# DRV2605.net
KiCad netlist of a schematic drawn in EAGLE
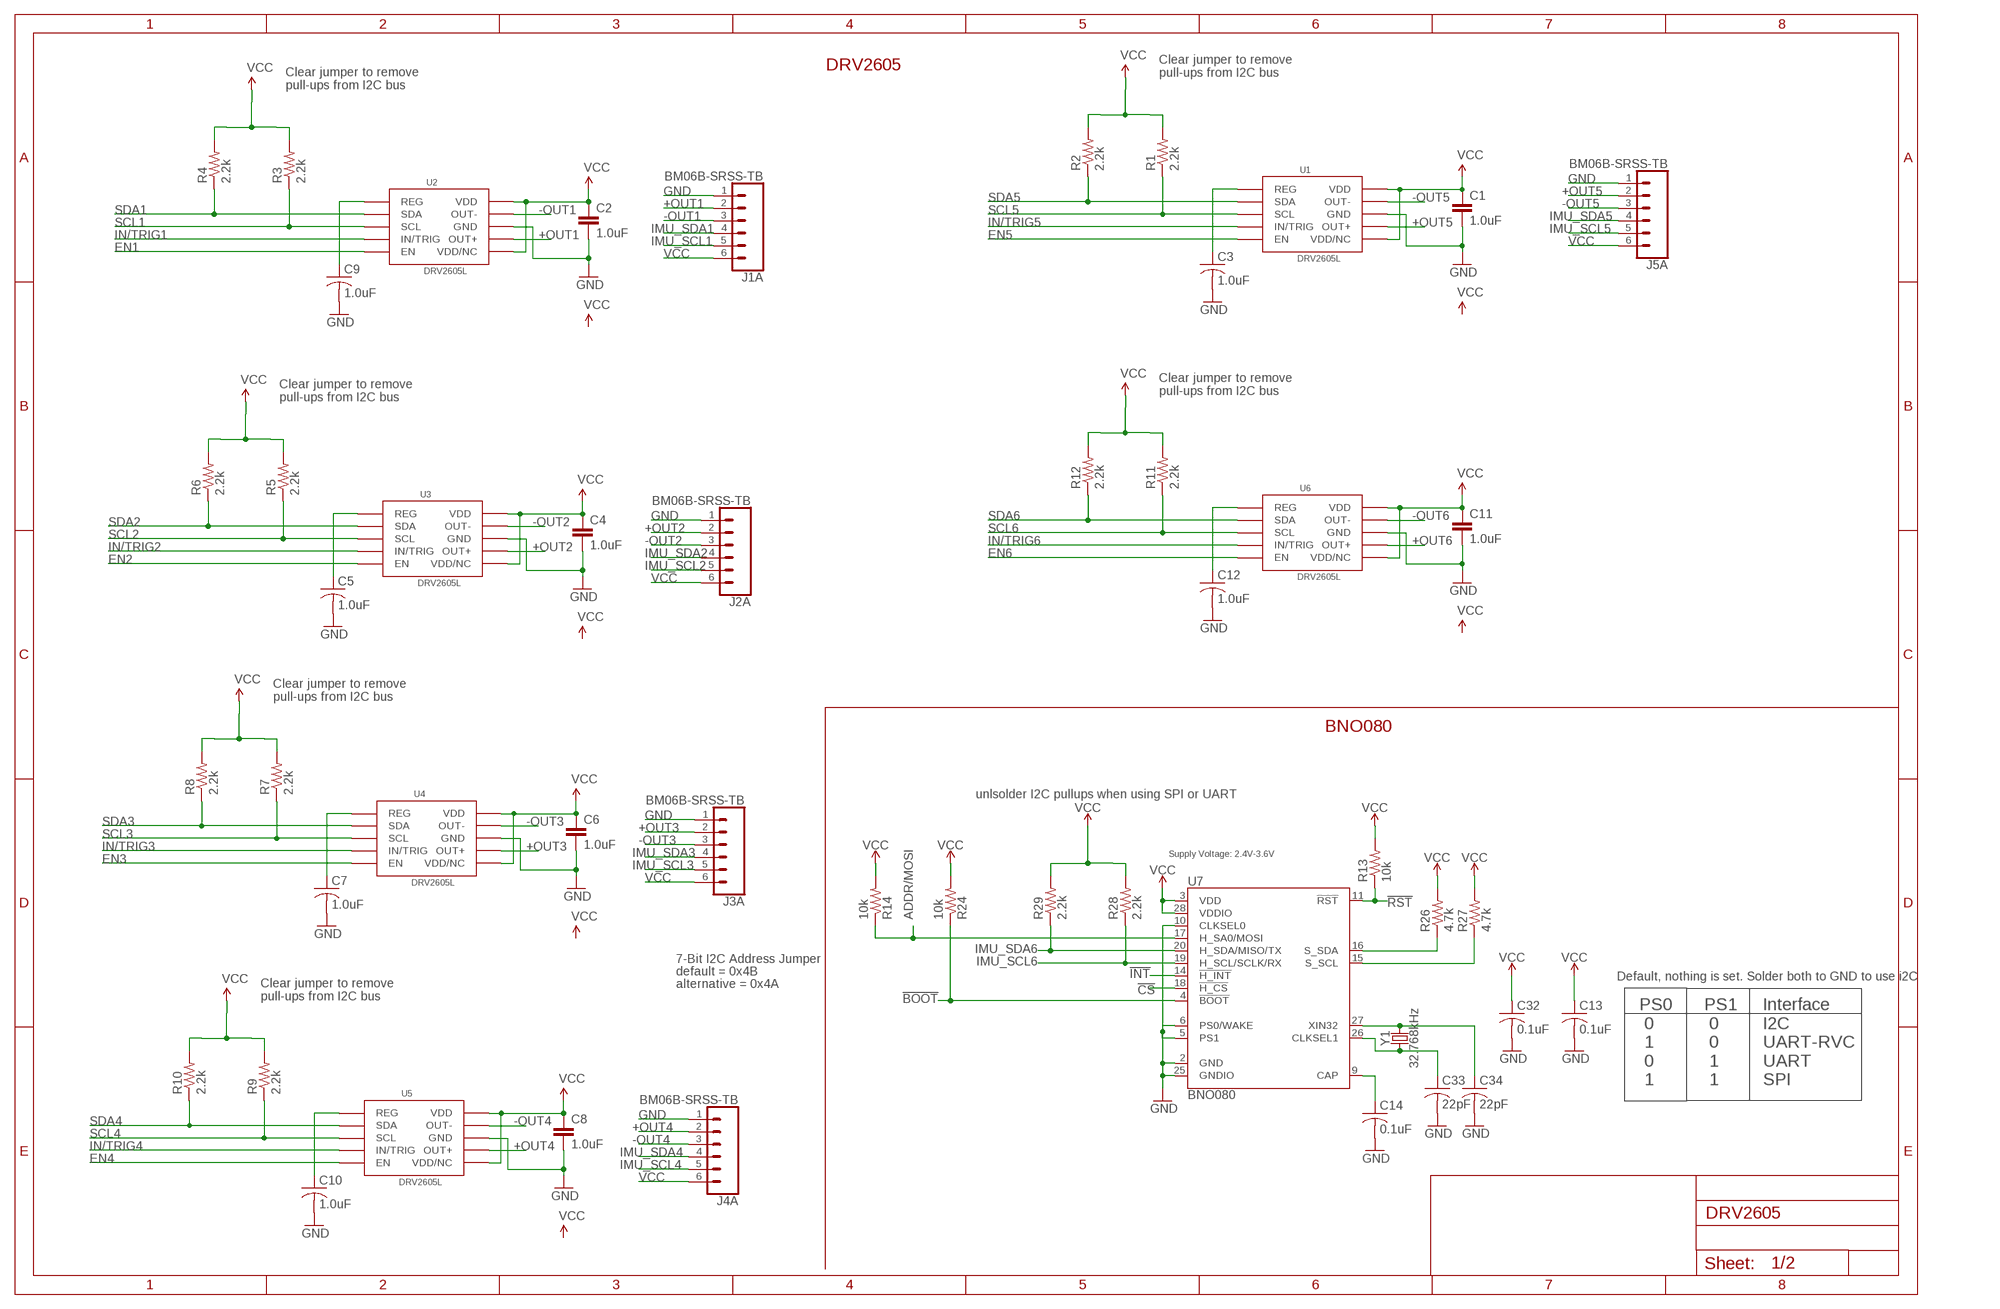
[diagram p0: schematic, sheet 1]
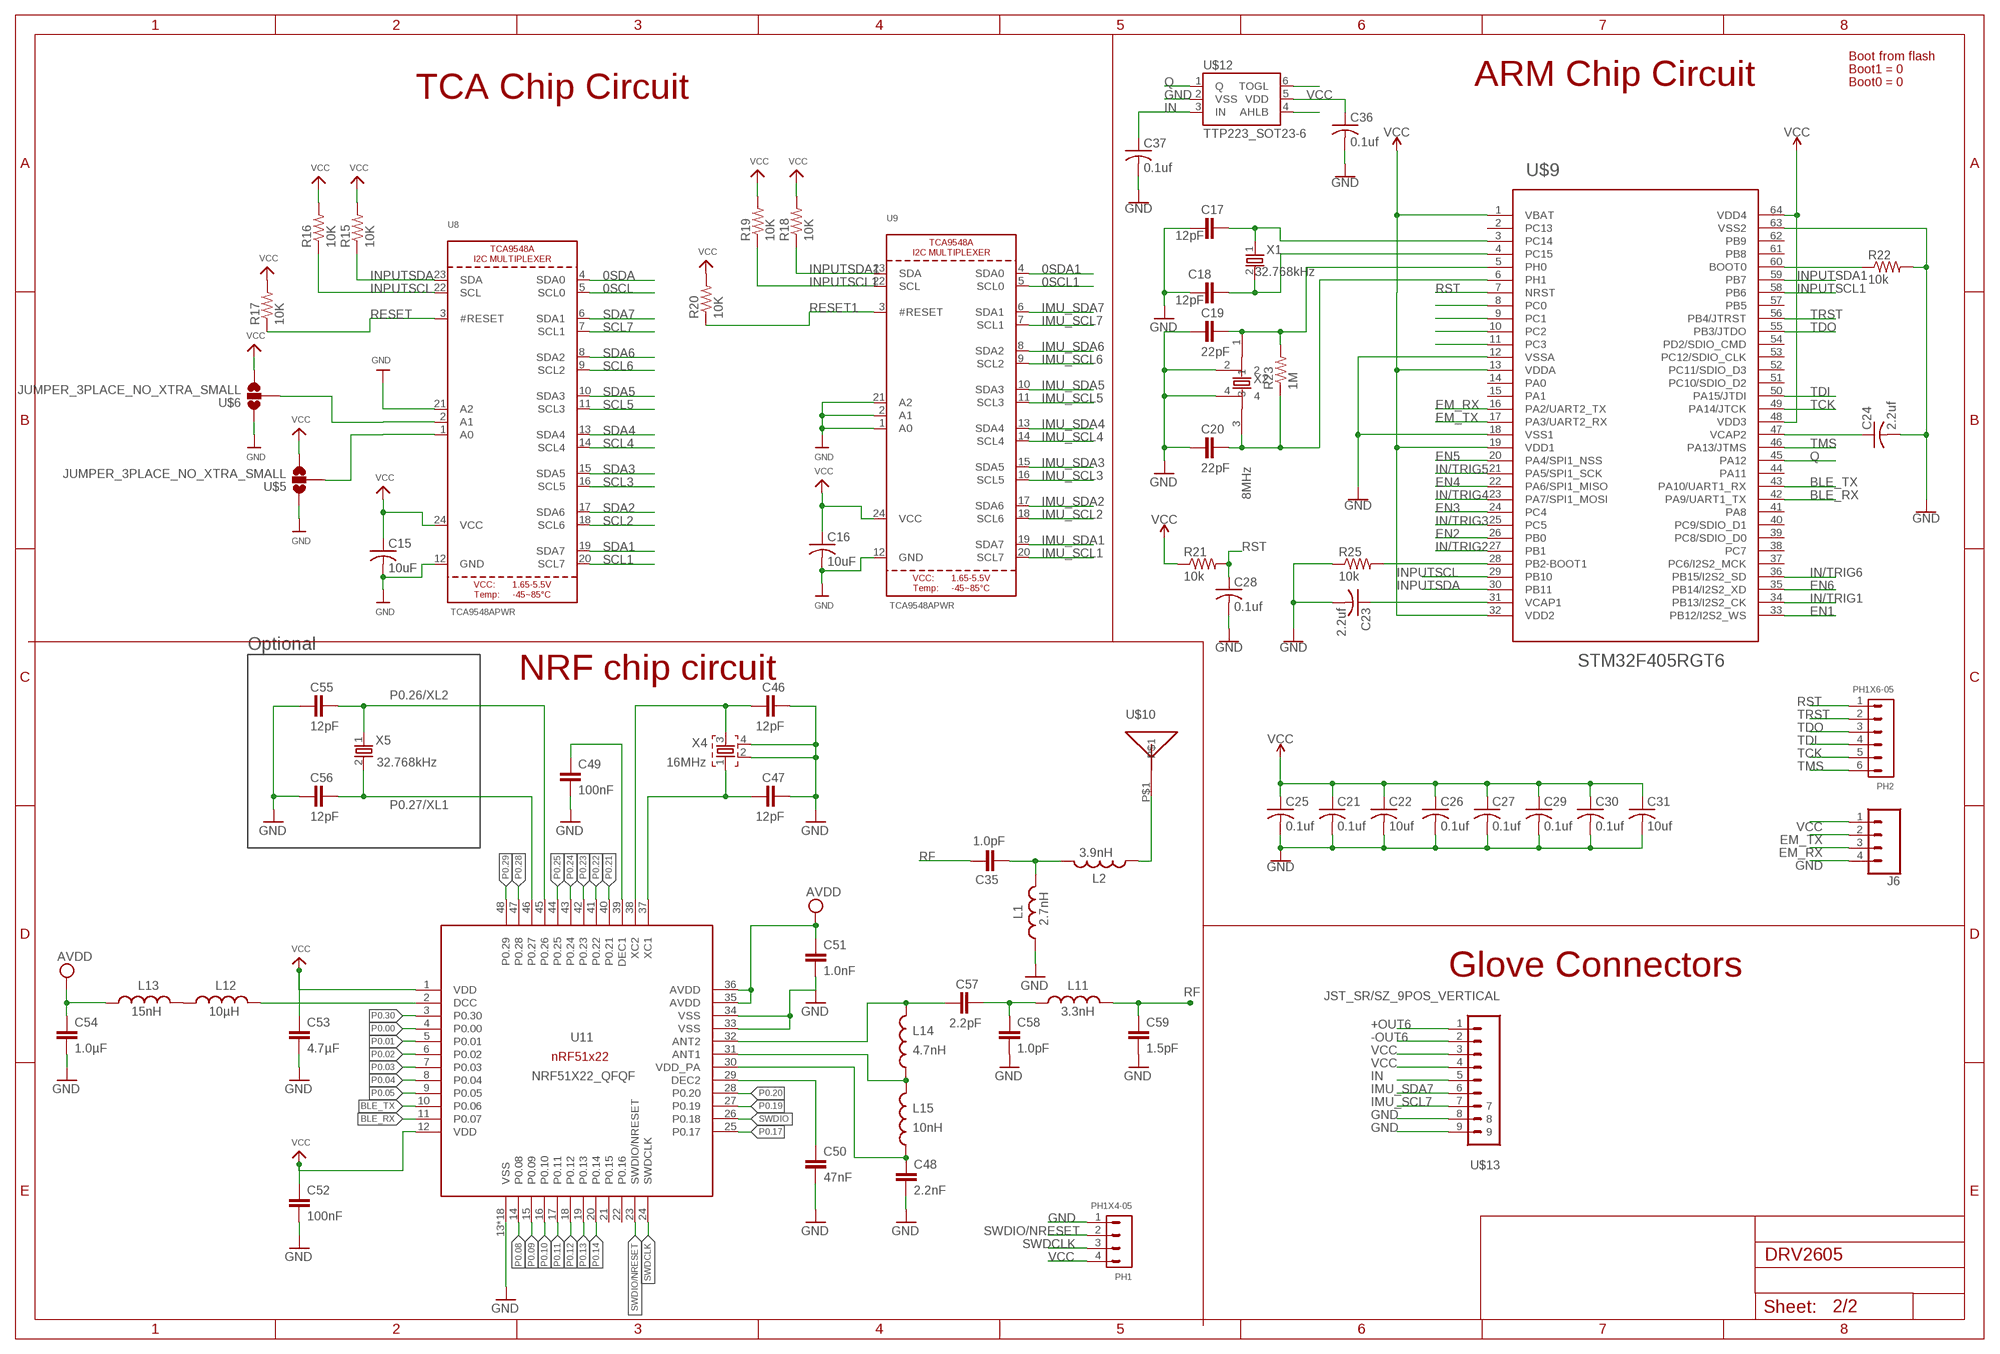
[diagram p1: schematic, sheet 2]

(export (version "E")
  (design (tool "Eeschema 10.0.6"))
  (components
    (comp (ref "C15")
      (value "10uF")
      (footprint "eagle-import:C0402")
      (libsource (lib "eagle-import") (part "resistor_348_C-USC0402"))
    )
    (comp (ref "C16")
      (value "10uF")
      (footprint "eagle-import:C0402")
      (libsource (lib "eagle-import") (part "resistor_348_C-USC0402"))
    )
    (comp (ref "C17")
      (value "12pF")
      (footprint "eagle-import:RESC0402_N")
      (libsource (lib "eagle-import") (part "CAPACITOR_0402_N"))
    )
    (comp (ref "C18")
      (value "12pF")
      (footprint "eagle-import:RESC0402_N")
      (libsource (lib "eagle-import") (part "CAPACITOR_0402_N"))
    )
    (comp (ref "C19")
      (value "22pF")
      (footprint "eagle-import:RESC0402_N")
      (libsource (lib "eagle-import") (part "CAPACITOR_0402_N"))
    )
    (comp (ref "C20")
      (value "22pF")
      (footprint "eagle-import:RESC0402_N")
      (libsource (lib "eagle-import") (part "CAPACITOR_0402_N"))
    )
    (comp (ref "C21")
      (value "0.1uf")
      (footprint "eagle-import:C0402")
      (libsource (lib "eagle-import") (part "C-USC0402"))
    )
    (comp (ref "C22")
      (value "10uf")
      (footprint "eagle-import:C0402")
      (libsource (lib "eagle-import") (part "C-USC0402"))
    )
    (comp (ref "C23")
      (value "2.2uf")
      (footprint "eagle-import:C0402")
      (libsource (lib "eagle-import") (part "C-USC0402"))
    )
    (comp (ref "C24")
      (value "2.2uf")
      (footprint "eagle-import:C0402")
      (libsource (lib "eagle-import") (part "C-USC0402"))
    )
    (comp (ref "C25")
      (value "0.1uf")
      (footprint "eagle-import:C0402")
      (libsource (lib "eagle-import") (part "C-USC0402"))
    )
    (comp (ref "C26")
      (value "0.1uf")
      (footprint "eagle-import:C0402")
      (libsource (lib "eagle-import") (part "C-USC0402"))
    )
    (comp (ref "C27")
      (value "0.1uf")
      (footprint "eagle-import:C0402")
      (libsource (lib "eagle-import") (part "C-USC0402"))
    )
    (comp (ref "C28")
      (value "0.1uf")
      (footprint "eagle-import:C0402")
      (libsource (lib "eagle-import") (part "C-USC0402"))
    )
    (comp (ref "C29")
      (value "0.1uf")
      (footprint "eagle-import:C0402")
      (libsource (lib "eagle-import") (part "C-USC0402"))
    )
    (comp (ref "C30")
      (value "0.1uf")
      (footprint "eagle-import:C0402")
      (libsource (lib "eagle-import") (part "C-USC0402"))
    )
    (comp (ref "C31")
      (value "10uf")
      (footprint "eagle-import:C0402")
      (libsource (lib "eagle-import") (part "C-USC0402"))
    )
    (comp (ref "C35")
      (value "1.0pF")
      (footprint "eagle-import:RESC0402_N")
      (libsource (lib "eagle-import") (part "CAPACITOR_0402_N"))
    )
    (comp (ref "C36")
      (value "0.1uf")
      (footprint "eagle-import:C0402")
      (libsource (lib "eagle-import") (part "C-USC0402"))
    )
    (comp (ref "C37")
      (value "0.1uf")
      (footprint "eagle-import:C0402")
      (libsource (lib "eagle-import") (part "C-USC0402"))
    )
    (comp (ref "C46")
      (value "12pF")
      (footprint "eagle-import:RESC0402_N")
      (libsource (lib "eagle-import") (part "CAPACITOR_0402_N"))
    )
    (comp (ref "C47")
      (value "12pF")
      (footprint "eagle-import:RESC0402_N")
      (libsource (lib "eagle-import") (part "CAPACITOR_0402_N"))
    )
    (comp (ref "C48")
      (value "2.2nF")
      (footprint "eagle-import:RESC0402_N")
      (libsource (lib "eagle-import") (part "CAPACITOR_0402_N"))
    )
    (comp (ref "C49")
      (value "100nF")
      (footprint "eagle-import:RESC0402_N")
      (libsource (lib "eagle-import") (part "CAPACITOR_0402_N"))
    )
    (comp (ref "C50")
      (value "47nF")
      (footprint "eagle-import:RESC0402_N")
      (libsource (lib "eagle-import") (part "CAPACITOR_0402_N"))
    )
    (comp (ref "C51")
      (value "1.0nF")
      (footprint "eagle-import:RESC0402_N")
      (libsource (lib "eagle-import") (part "CAPACITOR_0402_N"))
    )
    (comp (ref "C52")
      (value "100nF")
      (footprint "eagle-import:RESC0402_N")
      (libsource (lib "eagle-import") (part "CAPACITOR_0402_N"))
    )
    (comp (ref "C53")
      (value "4.7µF")
      (footprint "eagle-import:RESC0603_N")
      (libsource (lib "eagle-import") (part "CAPACITOR_0603_N"))
    )
    (comp (ref "C54")
      (value "1.0µF")
      (footprint "eagle-import:RESC0603_N")
      (libsource (lib "eagle-import") (part "CAPACITOR_0603_N"))
    )
    (comp (ref "C55")
      (value "12pF")
      (footprint "eagle-import:RESC0402_N")
      (libsource (lib "eagle-import") (part "CAPACITOR_0402_N"))
    )
    (comp (ref "C56")
      (value "12pF")
      (footprint "eagle-import:RESC0402_N")
      (libsource (lib "eagle-import") (part "CAPACITOR_0402_N"))
    )
    (comp (ref "C57")
      (value "2.2pF")
      (footprint "eagle-import:RESC0402_N")
      (libsource (lib "eagle-import") (part "CAPACITOR_0402_N"))
    )
    (comp (ref "C58")
      (value "1.0pF")
      (footprint "eagle-import:RESC0402_N")
      (libsource (lib "eagle-import") (part "CAPACITOR_0402_N"))
    )
    (comp (ref "C59")
      (value "1.5pF")
      (footprint "eagle-import:RESC0402_N")
      (libsource (lib "eagle-import") (part "CAPACITOR_0402_N"))
    )
    (comp (ref "J6")
      (value "CONN_04")
      (footprint "eagle-import:1X04")
      (libsource (lib "eagle-import") (part "CONN_04"))
    )
    (comp (ref "L1")
      (value "2.7nH")
      (footprint "eagle-import:RESC0402_N")
      (libsource (lib "eagle-import") (part "INDUCTOR_0402_N"))
    )
    (comp (ref "L2")
      (value "3.9nH")
      (footprint "eagle-import:RESC0402_N")
      (libsource (lib "eagle-import") (part "INDUCTOR_0402_N"))
    )
    (comp (ref "L11")
      (value "3.3nH")
      (footprint "eagle-import:RESC0402_N")
      (libsource (lib "eagle-import") (part "INDUCTOR_0402_N"))
    )
    (comp (ref "L12")
      (value "10µH")
      (footprint "eagle-import:RESC0603_N")
      (libsource (lib "eagle-import") (part "INDUCTOR_0603_N"))
    )
    (comp (ref "L13")
      (value "15nH")
      (footprint "eagle-import:RESC0402_N")
      (libsource (lib "eagle-import") (part "INDUCTOR_0402_N"))
    )
    (comp (ref "L14")
      (value "4.7nH")
      (footprint "eagle-import:RESC0402_N")
      (libsource (lib "eagle-import") (part "INDUCTOR_0402_N"))
    )
    (comp (ref "L15")
      (value "10nH")
      (footprint "eagle-import:RESC0402_N")
      (libsource (lib "eagle-import") (part "INDUCTOR_0402_N"))
    )
    (comp (ref "PH1")
      (value "PH1X4-05")
      (footprint "eagle-import:PH005-1-4")
      (libsource (lib "eagle-import") (part "PH1X4-05"))
    )
    (comp (ref "PH2")
      (value "PH1X6-05")
      (footprint "eagle-import:PH005-1-6")
      (libsource (lib "eagle-import") (part "PH1X6-05"))
    )
    (comp (ref "R15")
      (value "10K")
      (footprint "eagle-import:R0402")
      (libsource (lib "eagle-import") (part "R-US_R0402"))
    )
    (comp (ref "R16")
      (value "10K")
      (footprint "eagle-import:R0402")
      (libsource (lib "eagle-import") (part "R-US_R0402"))
    )
    (comp (ref "R17")
      (value "10K")
      (footprint "eagle-import:R0402")
      (libsource (lib "eagle-import") (part "R-US_R0402"))
    )
    (comp (ref "R18")
      (value "10K")
      (footprint "eagle-import:R0402")
      (libsource (lib "eagle-import") (part "R-US_R0402"))
    )
    (comp (ref "R19")
      (value "10K")
      (footprint "eagle-import:R0402")
      (libsource (lib "eagle-import") (part "R-US_R0402"))
    )
    (comp (ref "R20")
      (value "10K")
      (footprint "eagle-import:R0402")
      (libsource (lib "eagle-import") (part "R-US_R0402"))
    )
    (comp (ref "R21")
      (value "10k")
      (footprint "eagle-import:R0402")
      (libsource (lib "eagle-import") (part "resistor_348_R-US_R0402"))
    )
    (comp (ref "R22")
      (value "10k")
      (footprint "eagle-import:R0402")
      (libsource (lib "eagle-import") (part "resistor_348_R-US_R0402"))
    )
    (comp (ref "R23")
      (value "1M")
      (footprint "eagle-import:R0402")
      (libsource (lib "eagle-import") (part "resistor_348_R-US_R0402"))
    )
    (comp (ref "R25")
      (value "10k")
      (footprint "eagle-import:R0402")
      (libsource (lib "eagle-import") (part "resistor_348_R-US_R0402"))
    )
    (comp (ref "U$5")
      (value "JUMPER_3PLACE_NO_XTRA_SMALL")
      (footprint "eagle-import:XTRA_SMALL_JUMPER_3_NO")
      (libsource (lib "eagle-import") (part "JUMPER_3PLACE_NO_XTRA_SMALL"))
    )
    (comp (ref "U$6")
      (value "JUMPER_3PLACE_NO_XTRA_SMALL")
      (footprint "eagle-import:XTRA_SMALL_JUMPER_3_NO")
      (libsource (lib "eagle-import") (part "JUMPER_3PLACE_NO_XTRA_SMALL"))
    )
    (comp (ref "U$9")
      (value "STM32F405RGT6")
      (footprint "eagle-import:TQFP64")
      (libsource (lib "eagle-import") (part "STM32F405RG"))
    )
    (comp (ref "U$10")
      (value "ANT_2450AT18B100E")
      (footprint "eagle-import:2450AT18B100E")
      (libsource (lib "eagle-import") (part "ANT_2450AT18B100E"))
    )
    (comp (ref "U$12")
      (value "TTP223_SOT23-6")
      (footprint "eagle-import:SOT23-6")
      (libsource (lib "eagle-import") (part "TTP223_SOT23-6"))
    )
    (comp (ref "U$13")
      (value "JST_SR/SZ_9POS_VERTICAL")
      (footprint "eagle-import:JST_SR_SZ_VERTICA_9POS")
      (libsource (lib "eagle-import") (part "JST_SR/SZ_9POS_VERTICAL"))
    )
    (comp (ref "U8")
      (value "TCA9548APWR")
      (footprint "eagle-import:TSSOP24")
      (libsource (lib "eagle-import") (part "TCA9548A"))
    )
    (comp (ref "U9")
      (value "TCA9548APWR")
      (footprint "eagle-import:TSSOP24")
      (libsource (lib "eagle-import") (part "TCA9548A"))
    )
    (comp (ref "U11")
      (value "NRF51X22_QFQF")
      (footprint "eagle-import:QFN40P600X600X90-48_N")
      (libsource (lib "eagle-import") (part "NRF51X22_QFQF"))
    )
    (comp (ref "X1")
      (value "32.768kHz")
      (footprint "eagle-import:XTAL_3215_N")
      (libsource (lib "eagle-import") (part "XTAL_32KHZ"))
    )
    (comp (ref "X2")
      (value "8MHz")
      (footprint "eagle-import:CRYSTAL-SMD-5X3.2-4PAD")
      (libsource (lib "eagle-import") (part "CRYSTAL_5X3.2MM_4PAD"))
    )
    (comp (ref "X4")
      (value "16MHz")
      (footprint "eagle-import:BT-XTAL_2016_N")
      (libsource (lib "eagle-import") (part "XTAL_32MHZ"))
    )
    (comp (ref "X5")
      (value "32.768kHz")
      (footprint "eagle-import:XTAL_3215_N")
      (libsource (lib "eagle-import") (part "XTAL_32KHZ"))
    )
    (comp (ref "C1")
      (value "1.0uF")
      (footprint "eagle-import:0402-CAP")
      (libsource (lib "eagle-import") (part "1.0UF-16V-10%(0402)"))
    )
    (comp (ref "C2")
      (value "1.0uF")
      (footprint "eagle-import:0402-CAP")
      (libsource (lib "eagle-import") (part "1.0UF-16V-10%(0402)"))
    )
    (comp (ref "C3")
      (value "1.0uF")
      (footprint "eagle-import:C0402")
      (libsource (lib "eagle-import") (part "C-USC0402"))
    )
    (comp (ref "C4")
      (value "1.0uF")
      (footprint "eagle-import:0402-CAP")
      (libsource (lib "eagle-import") (part "1.0UF-16V-10%(0402)"))
    )
    (comp (ref "C5")
      (value "1.0uF")
      (footprint "eagle-import:C0402")
      (libsource (lib "eagle-import") (part "C-USC0402"))
    )
    (comp (ref "C6")
      (value "1.0uF")
      (footprint "eagle-import:0402-CAP")
      (libsource (lib "eagle-import") (part "1.0UF-16V-10%(0402)"))
    )
    (comp (ref "C7")
      (value "1.0uF")
      (footprint "eagle-import:C0402")
      (libsource (lib "eagle-import") (part "C-USC0402"))
    )
    (comp (ref "C8")
      (value "1.0uF")
      (footprint "eagle-import:0402-CAP")
      (libsource (lib "eagle-import") (part "1.0UF-16V-10%(0402)"))
    )
    (comp (ref "C9")
      (value "1.0uF")
      (footprint "eagle-import:C0402")
      (libsource (lib "eagle-import") (part "C-USC0402"))
    )
    (comp (ref "C10")
      (value "1.0uF")
      (footprint "eagle-import:C0402")
      (libsource (lib "eagle-import") (part "C-USC0402"))
    )
    (comp (ref "C11")
      (value "1.0uF")
      (footprint "eagle-import:0402-CAP")
      (libsource (lib "eagle-import") (part "1.0UF-16V-10%(0402)"))
    )
    (comp (ref "C12")
      (value "1.0uF")
      (footprint "eagle-import:C0402")
      (libsource (lib "eagle-import") (part "C-USC0402"))
    )
    (comp (ref "C13")
      (value "0.1uF")
      (footprint "eagle-import:C0402")
      (libsource (lib "eagle-import") (part "C-USC0402"))
    )
    (comp (ref "C14")
      (value "0.1uF")
      (footprint "eagle-import:C0402")
      (libsource (lib "eagle-import") (part "C-USC0402"))
    )
    (comp (ref "C32")
      (value "0.1uF")
      (footprint "eagle-import:C0402")
      (libsource (lib "eagle-import") (part "C-USC0402"))
    )
    (comp (ref "C33")
      (value "22pF")
      (footprint "eagle-import:C0402")
      (libsource (lib "eagle-import") (part "C-USC0402"))
    )
    (comp (ref "C34")
      (value "22pF")
      (footprint "eagle-import:C0402")
      (libsource (lib "eagle-import") (part "C-USC0402"))
    )
    (comp (ref "J1")
      (value "BM06B-SRSS-TB")
      (footprint "eagle-import:JST-6-SMD-HORI-1.0MM")
      (libsource (lib "eagle-import") (part "JST_6_PIN_HORIZONTAL"))
    )
    (comp (ref "J2")
      (value "BM06B-SRSS-TB")
      (footprint "eagle-import:JST-6-SMD-HORI-1.0MM")
      (libsource (lib "eagle-import") (part "JST_6_PIN_HORIZONTAL"))
    )
    (comp (ref "J3")
      (value "BM06B-SRSS-TB")
      (footprint "eagle-import:JST-6-SMD-HORI-1.0MM")
      (libsource (lib "eagle-import") (part "JST_6_PIN_HORIZONTAL"))
    )
    (comp (ref "J4")
      (value "BM06B-SRSS-TB")
      (footprint "eagle-import:JST-6-SMD-HORI-1.0MM")
      (libsource (lib "eagle-import") (part "JST_6_PIN_HORIZONTAL"))
    )
    (comp (ref "J5")
      (value "BM06B-SRSS-TB")
      (footprint "eagle-import:JST-6-SMD-HORI-1.0MM")
      (libsource (lib "eagle-import") (part "JST_6_PIN_HORIZONTAL"))
    )
    (comp (ref "R1")
      (value "2.2k")
      (footprint "eagle-import:0603-RES")
      (libsource (lib "eagle-import") (part "2.2KOHM-1/10W-1%(0603)"))
    )
    (comp (ref "R2")
      (value "2.2k")
      (footprint "eagle-import:0603-RES")
      (libsource (lib "eagle-import") (part "2.2KOHM-1/10W-1%(0603)"))
    )
    (comp (ref "R3")
      (value "2.2k")
      (footprint "eagle-import:0603-RES")
      (libsource (lib "eagle-import") (part "2.2KOHM-1/10W-1%(0603)"))
    )
    (comp (ref "R4")
      (value "2.2k")
      (footprint "eagle-import:0603-RES")
      (libsource (lib "eagle-import") (part "2.2KOHM-1/10W-1%(0603)"))
    )
    (comp (ref "R5")
      (value "2.2k")
      (footprint "eagle-import:0603-RES")
      (libsource (lib "eagle-import") (part "2.2KOHM-1/10W-1%(0603)"))
    )
    (comp (ref "R6")
      (value "2.2k")
      (footprint "eagle-import:0603-RES")
      (libsource (lib "eagle-import") (part "2.2KOHM-1/10W-1%(0603)"))
    )
    (comp (ref "R7")
      (value "2.2k")
      (footprint "eagle-import:0603-RES")
      (libsource (lib "eagle-import") (part "2.2KOHM-1/10W-1%(0603)"))
    )
    (comp (ref "R8")
      (value "2.2k")
      (footprint "eagle-import:0603-RES")
      (libsource (lib "eagle-import") (part "2.2KOHM-1/10W-1%(0603)"))
    )
    (comp (ref "R9")
      (value "2.2k")
      (footprint "eagle-import:0603-RES")
      (libsource (lib "eagle-import") (part "2.2KOHM-1/10W-1%(0603)"))
    )
    (comp (ref "R10")
      (value "2.2k")
      (footprint "eagle-import:0603-RES")
      (libsource (lib "eagle-import") (part "2.2KOHM-1/10W-1%(0603)"))
    )
    (comp (ref "R11")
      (value "2.2k")
      (footprint "eagle-import:0603-RES")
      (libsource (lib "eagle-import") (part "2.2KOHM-1/10W-1%(0603)"))
    )
    (comp (ref "R12")
      (value "2.2k")
      (footprint "eagle-import:0603-RES")
      (libsource (lib "eagle-import") (part "2.2KOHM-1/10W-1%(0603)"))
    )
    (comp (ref "R13")
      (value "10k")
      (footprint "eagle-import:R0402")
      (libsource (lib "eagle-import") (part "R-US_R0402"))
    )
    (comp (ref "R14")
      (value "10k")
      (footprint "eagle-import:R0402")
      (libsource (lib "eagle-import") (part "R-US_R0402"))
    )
    (comp (ref "R24")
      (value "10k")
      (footprint "eagle-import:R0402")
      (libsource (lib "eagle-import") (part "R-US_R0402"))
    )
    (comp (ref "R26")
      (value "4.7k")
      (footprint "eagle-import:R0402")
      (libsource (lib "eagle-import") (part "R-US_R0402"))
    )
    (comp (ref "R27")
      (value "4.7k")
      (footprint "eagle-import:R0402")
      (libsource (lib "eagle-import") (part "R-US_R0402"))
    )
    (comp (ref "R28")
      (value "2.2k")
      (footprint "eagle-import:R0402")
      (libsource (lib "eagle-import") (part "R-US_R0402"))
    )
    (comp (ref "R29")
      (value "2.2k")
      (footprint "eagle-import:R0402")
      (libsource (lib "eagle-import") (part "R-US_R0402"))
    )
    (comp (ref "U1")
      (value "DRV2605L")
      (footprint "eagle-import:VSSOP-10")
      (libsource (lib "eagle-import") (part "DRV2605L"))
    )
    (comp (ref "U2")
      (value "DRV2605L")
      (footprint "eagle-import:VSSOP-10")
      (libsource (lib "eagle-import") (part "DRV2605L"))
    )
    (comp (ref "U3")
      (value "DRV2605L")
      (footprint "eagle-import:VSSOP-10")
      (libsource (lib "eagle-import") (part "DRV2605L"))
    )
    (comp (ref "U4")
      (value "DRV2605L")
      (footprint "eagle-import:VSSOP-10")
      (libsource (lib "eagle-import") (part "DRV2605L"))
    )
    (comp (ref "U5")
      (value "DRV2605L")
      (footprint "eagle-import:VSSOP-10")
      (libsource (lib "eagle-import") (part "DRV2605L"))
    )
    (comp (ref "U6")
      (value "DRV2605L")
      (footprint "eagle-import:VSSOP-10")
      (libsource (lib "eagle-import") (part "DRV2605L"))
    )
    (comp (ref "U7")
      (value "BNO080")
      (footprint "eagle-import:LGA-28")
      (libsource (lib "eagle-import") (part "BNO080"))
    )
    (comp (ref "Y1")
      (value "32.768kHz")
      (footprint "eagle-import:CRYSTAL-SMD-3.2X1.5MM")
      (libsource (lib "eagle-import") (part "CRYSTAL-32.768KHZSMD-3.2X1.5"))
    )
  )
  (nets
    (net (code "1") (name "+OUT1") (class "Default")
      (node (ref "J1") (pin "2") (pinfunction "2_2") (pintype "passive"))
      (node (ref "U2") (pin "P$7") (pinfunction "OUT+_P$7") (pintype "bidirectional"))
    )
    (net (code "2") (name "+OUT2") (class "Default")
      (node (ref "J2") (pin "2") (pinfunction "2_2") (pintype "passive"))
      (node (ref "U3") (pin "P$7") (pinfunction "OUT+_P$7") (pintype "bidirectional"))
    )
    (net (code "3") (name "+OUT3") (class "Default")
      (node (ref "J3") (pin "2") (pinfunction "2_2") (pintype "passive"))
      (node (ref "U4") (pin "P$7") (pinfunction "OUT+_P$7") (pintype "bidirectional"))
    )
    (net (code "4") (name "+OUT4") (class "Default")
      (node (ref "J4") (pin "2") (pinfunction "2_2") (pintype "passive"))
      (node (ref "U5") (pin "P$7") (pinfunction "OUT+_P$7") (pintype "bidirectional"))
    )
    (net (code "5") (name "+OUT5") (class "Default")
      (node (ref "J5") (pin "2") (pinfunction "2_2") (pintype "passive"))
      (node (ref "U1") (pin "P$7") (pinfunction "OUT+_P$7") (pintype "bidirectional"))
    )
    (net (code "6") (name "+OUT6") (class "Default")
      (node (ref "U$13") (pin "1") (pinfunction "1_1") (pintype "passive"))
      (node (ref "U6") (pin "P$7") (pinfunction "OUT+_P$7") (pintype "bidirectional"))
    )
    (net (code "7") (name "-OUT1") (class "Default")
      (node (ref "J1") (pin "3") (pinfunction "3_3") (pintype "passive"))
      (node (ref "U2") (pin "P$9") (pinfunction "OUT-_P$9") (pintype "bidirectional"))
    )
    (net (code "8") (name "-OUT2") (class "Default")
      (node (ref "J2") (pin "3") (pinfunction "3_3") (pintype "passive"))
      (node (ref "U3") (pin "P$9") (pinfunction "OUT-_P$9") (pintype "bidirectional"))
    )
    (net (code "9") (name "-OUT3") (class "Default")
      (node (ref "J3") (pin "3") (pinfunction "3_3") (pintype "passive"))
      (node (ref "U4") (pin "P$9") (pinfunction "OUT-_P$9") (pintype "bidirectional"))
    )
    (net (code "10") (name "-OUT4") (class "Default")
      (node (ref "J4") (pin "3") (pinfunction "3_3") (pintype "passive"))
      (node (ref "U5") (pin "P$9") (pinfunction "OUT-_P$9") (pintype "bidirectional"))
    )
    (net (code "11") (name "-OUT5") (class "Default")
      (node (ref "J5") (pin "3") (pinfunction "3_3") (pintype "passive"))
      (node (ref "U1") (pin "P$9") (pinfunction "OUT-_P$9") (pintype "bidirectional"))
    )
    (net (code "12") (name "-OUT6") (class "Default")
      (node (ref "U$13") (pin "2") (pinfunction "2_2") (pintype "passive"))
      (node (ref "U6") (pin "P$9") (pinfunction "OUT-_P$9") (pintype "bidirectional"))
    )
    (net (code "13") (name "0SCL") (class "Default")
      (node (ref "U8") (pin "5") (pinfunction "SCL0_5") (pintype "bidirectional"))
    )
    (net (code "14") (name "0SCL1") (class "Default")
      (node (ref "U9") (pin "5") (pinfunction "SCL0_5") (pintype "bidirectional"))
    )
    (net (code "15") (name "0SDA") (class "Default")
      (node (ref "U8") (pin "4") (pinfunction "SDA0_4") (pintype "bidirectional"))
    )
    (net (code "16") (name "0SDA1") (class "Default")
      (node (ref "U9") (pin "4") (pinfunction "SDA0_4") (pintype "bidirectional"))
    )
    (net (code "17") (name "ADDR{slash}MOSI") (class "Default")
      (node (ref "R14") (pin "1") (pinfunction "1_1") (pintype "passive"))
      (node (ref "U7") (pin "17") (pinfunction "H_SA0/MOSI_17") (pintype "bidirectional"))
    )
    (net (code "18") (name "AVDD") (class "Default")
      (node (ref "C51") (pin "1") (pinfunction "1_1") (pintype "passive"))
      (node (ref "C54") (pin "1") (pinfunction "1_1") (pintype "passive"))
      (node (ref "L13") (pin "1") (pinfunction "1_1") (pintype "passive"))
      (node (ref "U11") (pin "35") (pinfunction "AVDD_35") (pintype "power_in"))
      (node (ref "U11") (pin "36") (pinfunction "AVDD_36") (pintype "power_in"))
    )
    (net (code "19") (name "BLE_RX") (class "Default")
      (node (ref "U$9") (pin "42") (pinfunction "PA9/UART1_TX_42") (pintype "bidirectional"))
      (node (ref "U11") (pin "11") (pinfunction "P0.07_11") (pintype "bidirectional"))
    )
    (net (code "20") (name "BLE_TX") (class "Default")
      (node (ref "U$9") (pin "43") (pinfunction "PA10/UART1_RX_43") (pintype "bidirectional"))
      (node (ref "U11") (pin "10") (pinfunction "P0.06_10") (pintype "bidirectional"))
    )
    (net (code "21") (name "EM_RX") (class "Default")
      (node (ref "J6") (pin "3") (pinfunction "3_3") (pintype "passive"))
      (node (ref "U$9") (pin "16") (pinfunction "PA2/UART2_TX_16") (pintype "bidirectional"))
    )
    (net (code "22") (name "EM_TX") (class "Default")
      (node (ref "J6") (pin "2") (pinfunction "2_2") (pintype "passive"))
      (node (ref "U$9") (pin "17") (pinfunction "PA3/UART2_RX_17") (pintype "bidirectional"))
    )
    (net (code "23") (name "EN1") (class "Default")
      (node (ref "U$9") (pin "33") (pinfunction "PB12/I2S2_WS_33") (pintype "bidirectional"))
      (node (ref "U2") (pin "P$5") (pinfunction "EN_P$5") (pintype "bidirectional"))
    )
    (net (code "24") (name "EN2") (class "Default")
      (node (ref "U$9") (pin "26") (pinfunction "PB0_26") (pintype "bidirectional"))
      (node (ref "U3") (pin "P$5") (pinfunction "EN_P$5") (pintype "bidirectional"))
    )
    (net (code "25") (name "EN3") (class "Default")
      (node (ref "U$9") (pin "24") (pinfunction "PC4_24") (pintype "bidirectional"))
      (node (ref "U4") (pin "P$5") (pinfunction "EN_P$5") (pintype "bidirectional"))
    )
    (net (code "26") (name "EN4") (class "Default")
      (node (ref "U$9") (pin "22") (pinfunction "PA6/SPI1_MISO_22") (pintype "bidirectional"))
      (node (ref "U5") (pin "P$5") (pinfunction "EN_P$5") (pintype "bidirectional"))
    )
    (net (code "27") (name "EN5") (class "Default")
      (node (ref "U$9") (pin "20") (pinfunction "PA4/SPI1_NSS_20") (pintype "bidirectional"))
      (node (ref "U1") (pin "P$5") (pinfunction "EN_P$5") (pintype "bidirectional"))
    )
    (net (code "28") (name "EN6") (class "Default")
      (node (ref "U$9") (pin "35") (pinfunction "PB14/I2S2_XD_35") (pintype "bidirectional"))
      (node (ref "U6") (pin "P$5") (pinfunction "EN_P$5") (pintype "bidirectional"))
    )
    (net (code "29") (name "GND") (class "Default")
      (node (ref "C1") (pin "2") (pinfunction "2_2") (pintype "passive"))
      (node (ref "C10") (pin "2") (pinfunction "2_2") (pintype "passive"))
      (node (ref "C11") (pin "2") (pinfunction "2_2") (pintype "passive"))
      (node (ref "C12") (pin "2") (pinfunction "2_2") (pintype "passive"))
      (node (ref "C13") (pin "2") (pinfunction "2_2") (pintype "passive"))
      (node (ref "C14") (pin "2") (pinfunction "2_2") (pintype "passive"))
      (node (ref "C15") (pin "2") (pinfunction "2_2") (pintype "passive"))
      (node (ref "C16") (pin "2") (pinfunction "2_2") (pintype "passive"))
      (node (ref "C17") (pin "1") (pinfunction "1_1") (pintype "passive"))
      (node (ref "C18") (pin "1") (pinfunction "1_1") (pintype "passive"))
      (node (ref "C19") (pin "1") (pinfunction "1_1") (pintype "passive"))
      (node (ref "C2") (pin "2") (pinfunction "2_2") (pintype "passive"))
      (node (ref "C20") (pin "1") (pinfunction "1_1") (pintype "passive"))
      (node (ref "C21") (pin "2") (pinfunction "2_2") (pintype "passive"))
      (node (ref "C22") (pin "2") (pinfunction "2_2") (pintype "passive"))
      (node (ref "C23") (pin "2") (pinfunction "2_2") (pintype "passive"))
      (node (ref "C24") (pin "2") (pinfunction "2_2") (pintype "passive"))
      (node (ref "C25") (pin "2") (pinfunction "2_2") (pintype "passive"))
      (node (ref "C26") (pin "2") (pinfunction "2_2") (pintype "passive"))
      (node (ref "C27") (pin "2") (pinfunction "2_2") (pintype "passive"))
      (node (ref "C28") (pin "2") (pinfunction "2_2") (pintype "passive"))
      (node (ref "C29") (pin "2") (pinfunction "2_2") (pintype "passive"))
      (node (ref "C3") (pin "2") (pinfunction "2_2") (pintype "passive"))
      (node (ref "C30") (pin "2") (pinfunction "2_2") (pintype "passive"))
      (node (ref "C31") (pin "2") (pinfunction "2_2") (pintype "passive"))
      (node (ref "C32") (pin "2") (pinfunction "2_2") (pintype "passive"))
      (node (ref "C33") (pin "2") (pinfunction "2_2") (pintype "passive"))
      (node (ref "C34") (pin "2") (pinfunction "2_2") (pintype "passive"))
      (node (ref "C36") (pin "2") (pinfunction "2_2") (pintype "passive"))
      (node (ref "C37") (pin "2") (pinfunction "2_2") (pintype "passive"))
      (node (ref "C4") (pin "2") (pinfunction "2_2") (pintype "passive"))
      (node (ref "C46") (pin "2") (pinfunction "2_2") (pintype "passive"))
      (node (ref "C47") (pin "2") (pinfunction "2_2") (pintype "passive"))
      (node (ref "C48") (pin "2") (pinfunction "2_2") (pintype "passive"))
      (node (ref "C49") (pin "2") (pinfunction "2_2") (pintype "passive"))
      (node (ref "C5") (pin "2") (pinfunction "2_2") (pintype "passive"))
      (node (ref "C50") (pin "2") (pinfunction "2_2") (pintype "passive"))
      (node (ref "C51") (pin "2") (pinfunction "2_2") (pintype "passive"))
      (node (ref "C52") (pin "2") (pinfunction "2_2") (pintype "passive"))
      (node (ref "C53") (pin "2") (pinfunction "2_2") (pintype "passive"))
      (node (ref "C54") (pin "2") (pinfunction "2_2") (pintype "passive"))
      (node (ref "C55") (pin "1") (pinfunction "1_1") (pintype "passive"))
      (node (ref "C56") (pin "1") (pinfunction "1_1") (pintype "passive"))
      (node (ref "C58") (pin "2") (pinfunction "2_2") (pintype "passive"))
      (node (ref "C59") (pin "2") (pinfunction "2_2") (pintype "passive"))
      (node (ref "C6") (pin "2") (pinfunction "2_2") (pintype "passive"))
      (node (ref "C7") (pin "2") (pinfunction "2_2") (pintype "passive"))
      (node (ref "C8") (pin "2") (pinfunction "2_2") (pintype "passive"))
      (node (ref "C9") (pin "2") (pinfunction "2_2") (pintype "passive"))
      (node (ref "J1") (pin "1") (pinfunction "1_1") (pintype "passive"))
      (node (ref "J2") (pin "1") (pinfunction "1_1") (pintype "passive"))
      (node (ref "J3") (pin "1") (pinfunction "1_1") (pintype "passive"))
      (node (ref "J4") (pin "1") (pinfunction "1_1") (pintype "passive"))
      (node (ref "J5") (pin "1") (pinfunction "1_1") (pintype "passive"))
      (node (ref "J6") (pin "4") (pinfunction "4_4") (pintype "passive"))
      (node (ref "L1") (pin "1") (pinfunction "1_1") (pintype "passive"))
      (node (ref "PH1") (pin "1") (pinfunction "1_1") (pintype "bidirectional"))
      (node (ref "R22") (pin "2") (pinfunction "2_2") (pintype "passive"))
      (node (ref "R25") (pin "1") (pinfunction "1_1") (pintype "passive"))
      (node (ref "U$12") (pin "2") (pinfunction "VSS_2") (pintype "bidirectional"))
      (node (ref "U$13") (pin "8") (pinfunction "8_8") (pintype "bidirectional"))
      (node (ref "U$13") (pin "9") (pinfunction "9_9") (pintype "bidirectional"))
      (node (ref "U$5") (pin "1") (pinfunction "1_1") (pintype "passive"))
      (node (ref "U$6") (pin "1") (pinfunction "1_1") (pintype "passive"))
      (node (ref "U$9") (pin "12") (pinfunction "VSSA_12") (pintype "bidirectional"))
      (node (ref "U$9") (pin "18") (pinfunction "VSS1_18") (pintype "bidirectional"))
      (node (ref "U$9") (pin "63") (pinfunction "VSS2_63") (pintype "bidirectional"))
      (node (ref "U1") (pin "P$8") (pinfunction "GND_P$8") (pintype "bidirectional"))
      (node (ref "U11") (pin "13") (pinfunction "VSS_13") (pintype "power_in"))
      (node (ref "U11") (pin "33") (pinfunction "VSS_33") (pintype "power_in"))
      (node (ref "U11") (pin "34") (pinfunction "VSS_34") (pintype "power_in"))
      (node (ref "U11") (pin "PAD") (pinfunction "VSS_PAD") (pintype "power_in"))
      (node (ref "U11") (pin "PAD@VIA01") (pinfunction "VSS_PAD@VIA01") (pintype "power_in"))
      (node (ref "U11") (pin "PAD@VIA02") (pinfunction "VSS_PAD@VIA02") (pintype "power_in"))
      (node (ref "U11") (pin "PAD@VIA03") (pinfunction "VSS_PAD@VIA03") (pintype "power_in"))
      (node (ref "U11") (pin "PAD@VIA04") (pinfunction "VSS_PAD@VIA04") (pintype "power_in"))
      (node (ref "U11") (pin "PAD@VIA05") (pinfunction "VSS_PAD@VIA05") (pintype "power_in"))
      (node (ref "U11") (pin "PAD@VIA06") (pinfunction "VSS_PAD@VIA06") (pintype "power_in"))
      (node (ref "U11") (pin "PAD@VIA07") (pinfunction "VSS_PAD@VIA07") (pintype "power_in"))
      (node (ref "U11") (pin "PAD@VIA08") (pinfunction "VSS_PAD@VIA08") (pintype "power_in"))
      (node (ref "U11") (pin "PAD@VIA09") (pinfunction "VSS_PAD@VIA09") (pintype "power_in"))
      (node (ref "U11") (pin "PAD@VIA10") (pinfunction "VSS_PAD@VIA10") (pintype "power_in"))
      (node (ref "U11") (pin "PAD@VIA11") (pinfunction "VSS_PAD@VIA11") (pintype "power_in"))
      (node (ref "U11") (pin "PAD@VIA12") (pinfunction "VSS_PAD@VIA12") (pintype "power_in"))
      (node (ref "U11") (pin "PAD@VIA13") (pinfunction "VSS_PAD@VIA13") (pintype "power_in"))
      (node (ref "U11") (pin "PAD@VIA14") (pinfunction "VSS_PAD@VIA14") (pintype "power_in"))
      (node (ref "U11") (pin "PAD@VIA15") (pinfunction "VSS_PAD@VIA15") (pintype "power_in"))
      (node (ref "U11") (pin "PAD@VIA16") (pinfunction "VSS_PAD@VIA16") (pintype "power_in"))
      (node (ref "U2") (pin "P$8") (pinfunction "GND_P$8") (pintype "bidirectional"))
      (node (ref "U3") (pin "P$8") (pinfunction "GND_P$8") (pintype "bidirectional"))
      (node (ref "U4") (pin "P$8") (pinfunction "GND_P$8") (pintype "bidirectional"))
      (node (ref "U5") (pin "P$8") (pinfunction "GND_P$8") (pintype "bidirectional"))
      (node (ref "U6") (pin "P$8") (pinfunction "GND_P$8") (pintype "bidirectional"))
      (node (ref "U7") (pin "10") (pinfunction "CLKSEL0_10") (pintype "bidirectional"))
      (node (ref "U7") (pin "2") (pinfunction "GND_2") (pintype "bidirectional"))
      (node (ref "U7") (pin "25") (pinfunction "GNDIO_25") (pintype "bidirectional"))
      (node (ref "U7") (pin "5") (pinfunction "PS1_5") (pintype "bidirectional"))
      (node (ref "U7") (pin "6") (pinfunction "PS0/WAKE_6") (pintype "bidirectional"))
      (node (ref "U8") (pin "12") (pinfunction "GND_12") (pintype "bidirectional"))
      (node (ref "U8") (pin "21") (pinfunction "A2_21") (pintype "bidirectional"))
      (node (ref "U9") (pin "1") (pinfunction "A0_1") (pintype "bidirectional"))
      (node (ref "U9") (pin "12") (pinfunction "GND_12") (pintype "bidirectional"))
      (node (ref "U9") (pin "2") (pinfunction "A1_2") (pintype "bidirectional"))
      (node (ref "U9") (pin "21") (pinfunction "A2_21") (pintype "bidirectional"))
      (node (ref "X2") (pin "2") (pinfunction "2_2") (pintype "bidirectional"))
      (node (ref "X2") (pin "4") (pinfunction "4_4") (pintype "bidirectional"))
      (node (ref "X4") (pin "2") (pinfunction "2_2") (pintype "passive"))
      (node (ref "X4") (pin "4") (pinfunction "4_4") (pintype "passive"))
    )
    (net (code "30") (name "IMU_SCL1") (class "Default")
      (node (ref "J1") (pin "5") (pinfunction "5_5") (pintype "passive"))
      (node (ref "U9") (pin "20") (pinfunction "SCL7_20") (pintype "bidirectional"))
    )
    (net (code "31") (name "IMU_SCL2") (class "Default")
      (node (ref "J2") (pin "5") (pinfunction "5_5") (pintype "passive"))
      (node (ref "U9") (pin "18") (pinfunction "SCL6_18") (pintype "bidirectional"))
    )
    (net (code "32") (name "IMU_SCL3") (class "Default")
      (node (ref "J3") (pin "5") (pinfunction "5_5") (pintype "passive"))
      (node (ref "U9") (pin "16") (pinfunction "SCL5_16") (pintype "bidirectional"))
    )
    (net (code "33") (name "IMU_SCL4") (class "Default")
      (node (ref "J4") (pin "5") (pinfunction "5_5") (pintype "passive"))
      (node (ref "U9") (pin "14") (pinfunction "SCL4_14") (pintype "bidirectional"))
    )
    (net (code "34") (name "IMU_SCL5") (class "Default")
      (node (ref "J5") (pin "5") (pinfunction "5_5") (pintype "passive"))
      (node (ref "U9") (pin "11") (pinfunction "SCL3_11") (pintype "bidirectional"))
    )
    (net (code "35") (name "IMU_SCL6") (class "Default")
      (node (ref "R28") (pin "1") (pinfunction "1_1") (pintype "passive"))
      (node (ref "U7") (pin "19") (pinfunction "H_SCL/SCLK/RX_19") (pintype "bidirectional"))
      (node (ref "U9") (pin "9") (pinfunction "SCL2_9") (pintype "bidirectional"))
    )
    (net (code "36") (name "IMU_SCL7") (class "Default")
      (node (ref "U$13") (pin "7") (pinfunction "7_7") (pintype "bidirectional"))
      (node (ref "U9") (pin "7") (pinfunction "SCL1_7") (pintype "bidirectional"))
    )
    (net (code "37") (name "IMU_SDA1") (class "Default")
      (node (ref "J1") (pin "4") (pinfunction "4_4") (pintype "passive"))
      (node (ref "U9") (pin "19") (pinfunction "SDA7_19") (pintype "bidirectional"))
    )
    (net (code "38") (name "IMU_SDA2") (class "Default")
      (node (ref "J2") (pin "4") (pinfunction "4_4") (pintype "passive"))
      (node (ref "U9") (pin "17") (pinfunction "SDA6_17") (pintype "bidirectional"))
    )
    (net (code "39") (name "IMU_SDA3") (class "Default")
      (node (ref "J3") (pin "4") (pinfunction "4_4") (pintype "passive"))
      (node (ref "U9") (pin "15") (pinfunction "SDA5_15") (pintype "bidirectional"))
    )
    (net (code "40") (name "IMU_SDA4") (class "Default")
      (node (ref "J4") (pin "4") (pinfunction "4_4") (pintype "passive"))
      (node (ref "U9") (pin "13") (pinfunction "SDA4_13") (pintype "bidirectional"))
    )
    (net (code "41") (name "IMU_SDA5") (class "Default")
      (node (ref "J5") (pin "4") (pinfunction "4_4") (pintype "passive"))
      (node (ref "U9") (pin "10") (pinfunction "SDA3_10") (pintype "bidirectional"))
    )
    (net (code "42") (name "IMU_SDA6") (class "Default")
      (node (ref "R29") (pin "1") (pinfunction "1_1") (pintype "passive"))
      (node (ref "U7") (pin "20") (pinfunction "H_SDA/MISO/TX_20") (pintype "bidirectional"))
      (node (ref "U9") (pin "8") (pinfunction "SDA2_8") (pintype "bidirectional"))
    )
    (net (code "43") (name "IMU_SDA7") (class "Default")
      (node (ref "U$13") (pin "6") (pinfunction "6_6") (pintype "passive"))
      (node (ref "U9") (pin "6") (pinfunction "SDA1_6") (pintype "bidirectional"))
    )
    (net (code "44") (name "IN") (class "Default")
      (node (ref "C37") (pin "1") (pinfunction "1_1") (pintype "passive"))
      (node (ref "U$12") (pin "3") (pinfunction "IN_3") (pintype "bidirectional"))
      (node (ref "U$13") (pin "5") (pinfunction "5_5") (pintype "passive"))
    )
    (net (code "45") (name "INPUTSCL") (class "Default")
      (node (ref "R16") (pin "1") (pinfunction "1_1") (pintype "passive"))
      (node (ref "U$9") (pin "29") (pinfunction "PB10_29") (pintype "bidirectional"))
      (node (ref "U8") (pin "22") (pinfunction "SCL_22") (pintype "bidirectional"))
    )
    (net (code "46") (name "INPUTSCL1") (class "Default")
      (node (ref "R19") (pin "1") (pinfunction "1_1") (pintype "passive"))
      (node (ref "U$9") (pin "58") (pinfunction "PB6_58") (pintype "bidirectional"))
      (node (ref "U9") (pin "22") (pinfunction "SCL_22") (pintype "bidirectional"))
    )
    (net (code "47") (name "INPUTSDA") (class "Default")
      (node (ref "R15") (pin "1") (pinfunction "1_1") (pintype "passive"))
      (node (ref "U$9") (pin "30") (pinfunction "PB11_30") (pintype "bidirectional"))
      (node (ref "U8") (pin "23") (pinfunction "SDA_23") (pintype "bidirectional"))
    )
    (net (code "48") (name "INPUTSDA1") (class "Default")
      (node (ref "R18") (pin "1") (pinfunction "1_1") (pintype "passive"))
      (node (ref "U$9") (pin "59") (pinfunction "PB7_59") (pintype "bidirectional"))
      (node (ref "U9") (pin "23") (pinfunction "SDA_23") (pintype "bidirectional"))
    )
    (net (code "49") (name "IN{slash}TRIG1") (class "Default")
      (node (ref "U$9") (pin "34") (pinfunction "PB13/I2S2_CK_34") (pintype "bidirectional"))
      (node (ref "U2") (pin "P$4") (pinfunction "IN/TRIG_P$4") (pintype "bidirectional"))
    )
    (net (code "50") (name "IN{slash}TRIG2") (class "Default")
      (node (ref "U$9") (pin "27") (pinfunction "PB1_27") (pintype "bidirectional"))
      (node (ref "U3") (pin "P$4") (pinfunction "IN/TRIG_P$4") (pintype "bidirectional"))
    )
    (net (code "51") (name "IN{slash}TRIG3") (class "Default")
      (node (ref "U$9") (pin "25") (pinfunction "PC5_25") (pintype "bidirectional"))
      (node (ref "U4") (pin "P$4") (pinfunction "IN/TRIG_P$4") (pintype "bidirectional"))
    )
    (net (code "52") (name "IN{slash}TRIG4") (class "Default")
      (node (ref "U$9") (pin "23") (pinfunction "PA7/SPI1_MOSI_23") (pintype "bidirectional"))
      (node (ref "U5") (pin "P$4") (pinfunction "IN/TRIG_P$4") (pintype "bidirectional"))
    )
    (net (code "53") (name "IN{slash}TRIG5") (class "Default")
      (node (ref "U$9") (pin "21") (pinfunction "PA5/SPI1_SCK_21") (pintype "bidirectional"))
      (node (ref "U1") (pin "P$4") (pinfunction "IN/TRIG_P$4") (pintype "bidirectional"))
    )
    (net (code "54") (name "IN{slash}TRIG6") (class "Default")
      (node (ref "U$9") (pin "36") (pinfunction "PB15/I2S2_SD_36") (pintype "bidirectional"))
      (node (ref "U6") (pin "P$4") (pinfunction "IN/TRIG_P$4") (pintype "bidirectional"))
    )
    (net (code "55") (name "Net-(C35-Pad1)") (class "Default")
      (node (ref "C35") (pin "1") (pinfunction "1_1") (pintype "passive"))
      (node (ref "L1") (pin "2") (pinfunction "2_2") (pintype "passive"))
      (node (ref "L2") (pin "2") (pinfunction "2_2") (pintype "passive"))
    )
    (net (code "56") (name "Net-(C57-Pad2)") (class "Default")
      (node (ref "C57") (pin "2") (pinfunction "2_2") (pintype "passive"))
      (node (ref "C58") (pin "1") (pinfunction "1_1") (pintype "passive"))
      (node (ref "L11") (pin "1") (pinfunction "1_1") (pintype "passive"))
    )
    (net (code "57") (name "Net-(L2-Pad1)") (class "Default")
      (node (ref "L2") (pin "1") (pinfunction "1_1") (pintype "passive"))
      (node (ref "U$10") (pin "P$1") (pinfunction "P$1_P$1") (pintype "bidirectional"))
    )
    (net (code "58") (name "Net-(L12-Pad1)") (class "Default")
      (node (ref "L12") (pin "1") (pinfunction "1_1") (pintype "passive"))
      (node (ref "L13") (pin "2") (pinfunction "2_2") (pintype "passive"))
    )
    (net (code "59") (name "Net-(U$9-BOOT0)") (class "Default")
      (node (ref "R22") (pin "1") (pinfunction "1_1") (pintype "passive"))
      (node (ref "U$9") (pin "60") (pinfunction "BOOT0_60") (pintype "bidirectional"))
    )
    (net (code "60") (name "Net-(U$9-PB2-BOOT1)") (class "Default")
      (node (ref "R25") (pin "2") (pinfunction "2_2") (pintype "passive"))
      (node (ref "U$9") (pin "28") (pinfunction "PB2-BOOT1_28") (pintype "bidirectional"))
    )
    (net (code "61") (name "Net-(U$9-PC14)") (class "Default")
      (node (ref "C17") (pin "2") (pinfunction "2_2") (pintype "passive"))
      (node (ref "U$9") (pin "3") (pinfunction "PC14_3") (pintype "bidirectional"))
      (node (ref "X1") (pin "1") (pinfunction "1_1") (pintype "passive"))
    )
    (net (code "62") (name "Net-(U$9-PC15)") (class "Default")
      (node (ref "C18") (pin "2") (pinfunction "2_2") (pintype "passive"))
      (node (ref "U$9") (pin "4") (pinfunction "PC15_4") (pintype "bidirectional"))
      (node (ref "X1") (pin "2") (pinfunction "2_2") (pintype "passive"))
    )
    (net (code "63") (name "Net-(U$9-PH0)") (class "Default")
      (node (ref "C19") (pin "2") (pinfunction "2_2") (pintype "passive"))
      (node (ref "R23") (pin "2") (pinfunction "2_2") (pintype "passive"))
      (node (ref "U$9") (pin "5") (pinfunction "PH0_5") (pintype "bidirectional"))
      (node (ref "X2") (pin "1") (pinfunction "1_1") (pintype "bidirectional"))
    )
    (net (code "64") (name "Net-(U$9-VCAP1)") (class "Default")
      (node (ref "C23") (pin "1") (pinfunction "1_1") (pintype "passive"))
      (node (ref "U$9") (pin "31") (pinfunction "VCAP1_31") (pintype "bidirectional"))
    )
    (net (code "65") (name "Net-(U$9-VCAP2)") (class "Default")
      (node (ref "C24") (pin "1") (pinfunction "1_1") (pintype "passive"))
      (node (ref "U$9") (pin "47") (pinfunction "VCAP2_47") (pintype "bidirectional"))
    )
    (net (code "66") (name "Net-(U1-REG)") (class "Default")
      (node (ref "C3") (pin "1") (pinfunction "1_1") (pintype "passive"))
      (node (ref "U1") (pin "P$1") (pinfunction "REG_P$1") (pintype "bidirectional"))
    )
    (net (code "67") (name "Net-(U2-REG)") (class "Default")
      (node (ref "C9") (pin "1") (pinfunction "1_1") (pintype "passive"))
      (node (ref "U2") (pin "P$1") (pinfunction "REG_P$1") (pintype "bidirectional"))
    )
    (net (code "68") (name "Net-(U3-REG)") (class "Default")
      (node (ref "C5") (pin "1") (pinfunction "1_1") (pintype "passive"))
      (node (ref "U3") (pin "P$1") (pinfunction "REG_P$1") (pintype "bidirectional"))
    )
    (net (code "69") (name "Net-(U4-REG)") (class "Default")
      (node (ref "C7") (pin "1") (pinfunction "1_1") (pintype "passive"))
      (node (ref "U4") (pin "P$1") (pinfunction "REG_P$1") (pintype "bidirectional"))
    )
    (net (code "70") (name "Net-(U5-REG)") (class "Default")
      (node (ref "C10") (pin "1") (pinfunction "1_1") (pintype "passive"))
      (node (ref "U5") (pin "P$1") (pinfunction "REG_P$1") (pintype "bidirectional"))
    )
    (net (code "71") (name "Net-(U6-REG)") (class "Default")
      (node (ref "C12") (pin "1") (pinfunction "1_1") (pintype "passive"))
      (node (ref "U6") (pin "P$1") (pinfunction "REG_P$1") (pintype "bidirectional"))
    )
    (net (code "72") (name "Net-(U7-CAP)") (class "Default")
      (node (ref "C14") (pin "1") (pinfunction "1_1") (pintype "passive"))
      (node (ref "U7") (pin "9") (pinfunction "CAP_9") (pintype "bidirectional"))
    )
    (net (code "73") (name "Net-(U7-CLKSEL1)") (class "Default")
      (node (ref "C33") (pin "1") (pinfunction "1_1") (pintype "passive"))
      (node (ref "U7") (pin "26") (pinfunction "CLKSEL1_26") (pintype "bidirectional"))
      (node (ref "Y1") (pin "P$1") (pinfunction "1_P$1") (pintype "passive"))
    )
    (net (code "74") (name "Net-(U7-S_SCL)") (class "Default")
      (node (ref "R27") (pin "1") (pinfunction "1_1") (pintype "passive"))
      (node (ref "U7") (pin "15") (pinfunction "S_SCL_15") (pintype "bidirectional"))
    )
    (net (code "75") (name "Net-(U7-S_SDA)") (class "Default")
      (node (ref "R26") (pin "1") (pinfunction "1_1") (pintype "passive"))
      (node (ref "U7") (pin "16") (pinfunction "S_SDA_16") (pintype "bidirectional"))
    )
    (net (code "76") (name "Net-(U7-XIN32)") (class "Default")
      (node (ref "C34") (pin "1") (pinfunction "1_1") (pintype "passive"))
      (node (ref "U7") (pin "27") (pinfunction "XIN32_27") (pintype "bidirectional"))
      (node (ref "Y1") (pin "P$2") (pinfunction "2_P$2") (pintype "passive"))
    )
    (net (code "77") (name "Net-(U8-A0)") (class "Default")
      (node (ref "U$5") (pin "2") (pinfunction "2_2") (pintype "passive"))
      (node (ref "U8") (pin "1") (pinfunction "A0_1") (pintype "bidirectional"))
    )
    (net (code "78") (name "Net-(U8-A1)") (class "Default")
      (node (ref "U$6") (pin "2") (pinfunction "2_2") (pintype "passive"))
      (node (ref "U8") (pin "2") (pinfunction "A1_2") (pintype "bidirectional"))
    )
    (net (code "79") (name "Net-(U11-ANT1)") (class "Default")
      (node (ref "L14") (pin "1") (pinfunction "1_1") (pintype "passive"))
      (node (ref "L15") (pin "2") (pinfunction "2_2") (pintype "passive"))
      (node (ref "U11") (pin "31") (pinfunction "ANT1_31") (pintype "bidirectional"))
    )
    (net (code "80") (name "Net-(U11-ANT2)") (class "Default")
      (node (ref "C57") (pin "1") (pinfunction "1_1") (pintype "passive"))
      (node (ref "L14") (pin "2") (pinfunction "2_2") (pintype "passive"))
      (node (ref "U11") (pin "32") (pinfunction "ANT2_32") (pintype "bidirectional"))
    )
    (net (code "81") (name "Net-(U11-DCC)") (class "Default")
      (node (ref "L12") (pin "2") (pinfunction "2_2") (pintype "passive"))
      (node (ref "U11") (pin "2") (pinfunction "DCC_2") (pintype "power_in"))
    )
    (net (code "82") (name "Net-(U11-DEC1)") (class "Default")
      (node (ref "C49") (pin "1") (pinfunction "1_1") (pintype "passive"))
      (node (ref "U11") (pin "39") (pinfunction "DEC1_39") (pintype "power_in"))
    )
    (net (code "83") (name "Net-(U11-DEC2)") (class "Default")
      (node (ref "C50") (pin "1") (pinfunction "1_1") (pintype "passive"))
      (node (ref "U11") (pin "29") (pinfunction "DEC2_29") (pintype "power_in"))
    )
    (net (code "84") (name "Net-(U11-VDD_PA)") (class "Default")
      (node (ref "C48") (pin "1") (pinfunction "1_1") (pintype "passive"))
      (node (ref "L15") (pin "1") (pinfunction "1_1") (pintype "passive"))
      (node (ref "U11") (pin "30") (pinfunction "VDD_PA_30") (pintype "power_in"))
    )
    (net (code "85") (name "Net-(U11-XC1)") (class "Default")
      (node (ref "C47") (pin "1") (pinfunction "1_1") (pintype "passive"))
      (node (ref "U11") (pin "37") (pinfunction "XC1_37") (pintype "bidirectional"))
      (node (ref "X4") (pin "1") (pinfunction "1_1") (pintype "passive"))
    )
    (net (code "86") (name "Net-(U11-XC2)") (class "Default")
      (node (ref "C46") (pin "1") (pinfunction "1_1") (pintype "passive"))
      (node (ref "U11") (pin "38") (pinfunction "XC2_38") (pintype "bidirectional"))
      (node (ref "X4") (pin "3") (pinfunction "3_3") (pintype "passive"))
    )
    (net (code "87") (name "P0.00") (class "Default")
      (node (ref "U11") (pin "4") (pinfunction "P0.00_4") (pintype "bidirectional"))
    )
    (net (code "88") (name "P0.01") (class "Default")
      (node (ref "U11") (pin "5") (pinfunction "P0.01_5") (pintype "bidirectional"))
    )
    (net (code "89") (name "P0.02") (class "Default")
      (node (ref "U11") (pin "6") (pinfunction "P0.02_6") (pintype "bidirectional"))
    )
    (net (code "90") (name "P0.03") (class "Default")
      (node (ref "U11") (pin "7") (pinfunction "P0.03_7") (pintype "bidirectional"))
    )
    (net (code "91") (name "P0.04") (class "Default")
      (node (ref "U11") (pin "8") (pinfunction "P0.04_8") (pintype "bidirectional"))
    )
    (net (code "92") (name "P0.05") (class "Default")
      (node (ref "U11") (pin "9") (pinfunction "P0.05_9") (pintype "bidirectional"))
    )
    (net (code "93") (name "P0.08") (class "Default")
      (node (ref "U11") (pin "14") (pinfunction "P0.08_14") (pintype "bidirectional"))
    )
    (net (code "94") (name "P0.09") (class "Default")
      (node (ref "U11") (pin "15") (pinfunction "P0.09_15") (pintype "bidirectional"))
    )
    (net (code "95") (name "P0.10") (class "Default")
      (node (ref "U11") (pin "16") (pinfunction "P0.10_16") (pintype "bidirectional"))
    )
    (net (code "96") (name "P0.11") (class "Default")
      (node (ref "U11") (pin "17") (pinfunction "P0.11_17") (pintype "bidirectional"))
    )
    (net (code "97") (name "P0.12") (class "Default")
      (node (ref "U11") (pin "18") (pinfunction "P0.12_18") (pintype "bidirectional"))
    )
    (net (code "98") (name "P0.13") (class "Default")
      (node (ref "U11") (pin "19") (pinfunction "P0.13_19") (pintype "bidirectional"))
    )
    (net (code "99") (name "P0.14") (class "Default")
      (node (ref "U11") (pin "20") (pinfunction "P0.14_20") (pintype "bidirectional"))
    )
    (net (code "100") (name "P0.17") (class "Default")
      (node (ref "U11") (pin "25") (pinfunction "P0.17_25") (pintype "bidirectional"))
    )
    (net (code "101") (name "P0.19") (class "Default")
      (node (ref "U11") (pin "27") (pinfunction "P0.19_27") (pintype "bidirectional"))
    )
    (net (code "102") (name "P0.20") (class "Default")
      (node (ref "U11") (pin "28") (pinfunction "P0.20_28") (pintype "bidirectional"))
    )
    (net (code "103") (name "P0.21") (class "Default")
      (node (ref "U11") (pin "40") (pinfunction "P0.21_40") (pintype "bidirectional"))
    )
    (net (code "104") (name "P0.22") (class "Default")
      (node (ref "U11") (pin "41") (pinfunction "P0.22_41") (pintype "bidirectional"))
    )
    (net (code "105") (name "P0.23") (class "Default")
      (node (ref "U11") (pin "42") (pinfunction "P0.23_42") (pintype "bidirectional"))
    )
    (net (code "106") (name "P0.24") (class "Default")
      (node (ref "U11") (pin "43") (pinfunction "P0.24_43") (pintype "bidirectional"))
    )
    (net (code "107") (name "P0.25") (class "Default")
      (node (ref "U11") (pin "44") (pinfunction "P0.25_44") (pintype "bidirectional"))
    )
    (net (code "108") (name "P0.26{slash}XL2") (class "Default")
      (node (ref "C55") (pin "2") (pinfunction "2_2") (pintype "passive"))
      (node (ref "U11") (pin "45") (pinfunction "P0.26_45") (pintype "bidirectional"))
      (node (ref "X5") (pin "1") (pinfunction "1_1") (pintype "passive"))
    )
    (net (code "109") (name "P0.27{slash}XL1") (class "Default")
      (node (ref "C56") (pin "2") (pinfunction "2_2") (pintype "passive"))
      (node (ref "U11") (pin "46") (pinfunction "P0.27_46") (pintype "bidirectional"))
      (node (ref "X5") (pin "2") (pinfunction "2_2") (pintype "passive"))
    )
    (net (code "110") (name "P0.28") (class "Default")
      (node (ref "U11") (pin "47") (pinfunction "P0.28_47") (pintype "bidirectional"))
    )
    (net (code "111") (name "P0.29") (class "Default")
      (node (ref "U11") (pin "48") (pinfunction "P0.29_48") (pintype "bidirectional"))
    )
    (net (code "112") (name "P0.30") (class "Default")
      (node (ref "U11") (pin "3") (pinfunction "P0.30_3") (pintype "bidirectional"))
    )
    (net (code "113") (name "PH1") (class "Default")
      (node (ref "C20") (pin "2") (pinfunction "2_2") (pintype "passive"))
      (node (ref "R23") (pin "1") (pinfunction "1_1") (pintype "passive"))
      (node (ref "U$9") (pin "6") (pinfunction "PH1_6") (pintype "bidirectional"))
      (node (ref "X2") (pin "3") (pinfunction "3_3") (pintype "bidirectional"))
    )
    (net (code "114") (name "Q") (class "Default")
      (node (ref "U$12") (pin "1") (pinfunction "Q_1") (pintype "bidirectional"))
      (node (ref "U$9") (pin "45") (pinfunction "PA12_45") (pintype "bidirectional"))
    )
    (net (code "115") (name "RESET") (class "Default")
      (node (ref "R17") (pin "1") (pinfunction "1_1") (pintype "passive"))
      (node (ref "U8") (pin "3") (pinfunction "#RESET_3") (pintype "bidirectional"))
    )
    (net (code "116") (name "RESET1") (class "Default")
      (node (ref "R20") (pin "1") (pinfunction "1_1") (pintype "passive"))
      (node (ref "U9") (pin "3") (pinfunction "#RESET_3") (pintype "bidirectional"))
    )
    (net (code "117") (name "RF") (class "Default")
      (node (ref "C35") (pin "2") (pinfunction "2_2") (pintype "passive"))
      (node (ref "C59") (pin "1") (pinfunction "1_1") (pintype "passive"))
      (node (ref "L11") (pin "2") (pinfunction "2_2") (pintype "passive"))
    )
    (net (code "118") (name "RST") (class "Default")
      (node (ref "C28") (pin "1") (pinfunction "1_1") (pintype "passive"))
      (node (ref "PH2") (pin "1") (pinfunction "1_1") (pintype "bidirectional"))
      (node (ref "R21") (pin "2") (pinfunction "2_2") (pintype "passive"))
      (node (ref "U$9") (pin "7") (pinfunction "NRST_7") (pintype "bidirectional"))
    )
    (net (code "119") (name "SCL1") (class "Default")
      (node (ref "R3") (pin "1") (pinfunction "1_1") (pintype "passive"))
      (node (ref "U2") (pin "P$2") (pinfunction "SCL_P$2") (pintype "bidirectional"))
      (node (ref "U8") (pin "20") (pinfunction "SCL7_20") (pintype "bidirectional"))
    )
    (net (code "120") (name "SCL2") (class "Default")
      (node (ref "R5") (pin "1") (pinfunction "1_1") (pintype "passive"))
      (node (ref "U3") (pin "P$2") (pinfunction "SCL_P$2") (pintype "bidirectional"))
      (node (ref "U8") (pin "18") (pinfunction "SCL6_18") (pintype "bidirectional"))
    )
    (net (code "121") (name "SCL3") (class "Default")
      (node (ref "R7") (pin "1") (pinfunction "1_1") (pintype "passive"))
      (node (ref "U4") (pin "P$2") (pinfunction "SCL_P$2") (pintype "bidirectional"))
      (node (ref "U8") (pin "16") (pinfunction "SCL5_16") (pintype "bidirectional"))
    )
    (net (code "122") (name "SCL4") (class "Default")
      (node (ref "R9") (pin "1") (pinfunction "1_1") (pintype "passive"))
      (node (ref "U5") (pin "P$2") (pinfunction "SCL_P$2") (pintype "bidirectional"))
      (node (ref "U8") (pin "14") (pinfunction "SCL4_14") (pintype "bidirectional"))
    )
    (net (code "123") (name "SCL5") (class "Default")
      (node (ref "R1") (pin "1") (pinfunction "1_1") (pintype "passive"))
      (node (ref "U1") (pin "P$2") (pinfunction "SCL_P$2") (pintype "bidirectional"))
      (node (ref "U8") (pin "11") (pinfunction "SCL3_11") (pintype "bidirectional"))
    )
    (net (code "124") (name "SCL6") (class "Default")
      (node (ref "R11") (pin "1") (pinfunction "1_1") (pintype "passive"))
      (node (ref "U6") (pin "P$2") (pinfunction "SCL_P$2") (pintype "bidirectional"))
      (node (ref "U8") (pin "9") (pinfunction "SCL2_9") (pintype "bidirectional"))
    )
    (net (code "125") (name "SCL7") (class "Default")
      (node (ref "U8") (pin "7") (pinfunction "SCL1_7") (pintype "bidirectional"))
    )
    (net (code "126") (name "SDA1") (class "Default")
      (node (ref "R4") (pin "1") (pinfunction "1_1") (pintype "passive"))
      (node (ref "U2") (pin "P$3") (pinfunction "SDA_P$3") (pintype "bidirectional"))
      (node (ref "U8") (pin "19") (pinfunction "SDA7_19") (pintype "bidirectional"))
    )
    (net (code "127") (name "SDA2") (class "Default")
      (node (ref "R6") (pin "1") (pinfunction "1_1") (pintype "passive"))
      (node (ref "U3") (pin "P$3") (pinfunction "SDA_P$3") (pintype "bidirectional"))
      (node (ref "U8") (pin "17") (pinfunction "SDA6_17") (pintype "bidirectional"))
    )
    (net (code "128") (name "SDA3") (class "Default")
      (node (ref "R8") (pin "1") (pinfunction "1_1") (pintype "passive"))
      (node (ref "U4") (pin "P$3") (pinfunction "SDA_P$3") (pintype "bidirectional"))
      (node (ref "U8") (pin "15") (pinfunction "SDA5_15") (pintype "bidirectional"))
    )
    (net (code "129") (name "SDA4") (class "Default")
      (node (ref "R10") (pin "1") (pinfunction "1_1") (pintype "passive"))
      (node (ref "U5") (pin "P$3") (pinfunction "SDA_P$3") (pintype "bidirectional"))
      (node (ref "U8") (pin "13") (pinfunction "SDA4_13") (pintype "bidirectional"))
    )
    (net (code "130") (name "SDA5") (class "Default")
      (node (ref "R2") (pin "1") (pinfunction "1_1") (pintype "passive"))
      (node (ref "U1") (pin "P$3") (pinfunction "SDA_P$3") (pintype "bidirectional"))
      (node (ref "U8") (pin "10") (pinfunction "SDA3_10") (pintype "bidirectional"))
    )
    (net (code "131") (name "SDA6") (class "Default")
      (node (ref "R12") (pin "1") (pinfunction "1_1") (pintype "passive"))
      (node (ref "U6") (pin "P$3") (pinfunction "SDA_P$3") (pintype "bidirectional"))
      (node (ref "U8") (pin "8") (pinfunction "SDA2_8") (pintype "bidirectional"))
    )
    (net (code "132") (name "SDA7") (class "Default")
      (node (ref "U8") (pin "6") (pinfunction "SDA1_6") (pintype "bidirectional"))
    )
    (net (code "133") (name "SWDCLK") (class "Default")
      (node (ref "PH1") (pin "3") (pinfunction "3_3") (pintype "bidirectional"))
      (node (ref "U11") (pin "24") (pinfunction "SWDCLK_24") (pintype "input"))
    )
    (net (code "134") (name "SWDIO") (class "Default")
      (node (ref "U11") (pin "26") (pinfunction "P0.18_26") (pintype "bidirectional"))
    )
    (net (code "135") (name "SWDIO{slash}NRESET") (class "Default")
      (node (ref "PH1") (pin "2") (pinfunction "2_2") (pintype "bidirectional"))
      (node (ref "U11") (pin "23") (pinfunction "SWDIO/NRESET_23") (pintype "bidirectional"))
    )
    (net (code "136") (name "TCK") (class "Default")
      (node (ref "PH2") (pin "5") (pinfunction "5_5") (pintype "bidirectional"))
      (node (ref "U$9") (pin "49") (pinfunction "PA14/JTCK_49") (pintype "bidirectional"))
    )
    (net (code "137") (name "TDI") (class "Default")
      (node (ref "PH2") (pin "4") (pinfunction "4_4") (pintype "bidirectional"))
      (node (ref "U$9") (pin "50") (pinfunction "PA15/JTDI_50") (pintype "bidirectional"))
    )
    (net (code "138") (name "TDO") (class "Default")
      (node (ref "PH2") (pin "3") (pinfunction "3_3") (pintype "bidirectional"))
      (node (ref "U$9") (pin "55") (pinfunction "PB3/JTDO_55") (pintype "bidirectional"))
    )
    (net (code "139") (name "TMS") (class "Default")
      (node (ref "PH2") (pin "6") (pinfunction "6_6") (pintype "bidirectional"))
      (node (ref "U$9") (pin "46") (pinfunction "PA13/JTMS_46") (pintype "bidirectional"))
    )
    (net (code "140") (name "TRST") (class "Default")
      (node (ref "PH2") (pin "2") (pinfunction "2_2") (pintype "bidirectional"))
      (node (ref "U$9") (pin "56") (pinfunction "PB4/JTRST_56") (pintype "bidirectional"))
    )
    (net (code "141") (name "VCC") (class "Default")
      (node (ref "C1") (pin "1") (pinfunction "1_1") (pintype "passive"))
      (node (ref "C11") (pin "1") (pinfunction "1_1") (pintype "passive"))
      (node (ref "C13") (pin "1") (pinfunction "1_1") (pintype "passive"))
      (node (ref "C15") (pin "1") (pinfunction "1_1") (pintype "passive"))
      (node (ref "C16") (pin "1") (pinfunction "1_1") (pintype "passive"))
      (node (ref "C2") (pin "1") (pinfunction "1_1") (pintype "passive"))
      (node (ref "C21") (pin "1") (pinfunction "1_1") (pintype "passive"))
      (node (ref "C22") (pin "1") (pinfunction "1_1") (pintype "passive"))
      (node (ref "C25") (pin "1") (pinfunction "1_1") (pintype "passive"))
      (node (ref "C26") (pin "1") (pinfunction "1_1") (pintype "passive"))
      (node (ref "C27") (pin "1") (pinfunction "1_1") (pintype "passive"))
      (node (ref "C29") (pin "1") (pinfunction "1_1") (pintype "passive"))
      (node (ref "C30") (pin "1") (pinfunction "1_1") (pintype "passive"))
      (node (ref "C31") (pin "1") (pinfunction "1_1") (pintype "passive"))
      (node (ref "C32") (pin "1") (pinfunction "1_1") (pintype "passive"))
      (node (ref "C36") (pin "1") (pinfunction "1_1") (pintype "passive"))
      (node (ref "C4") (pin "1") (pinfunction "1_1") (pintype "passive"))
      (node (ref "C52") (pin "1") (pinfunction "1_1") (pintype "passive"))
      (node (ref "C53") (pin "1") (pinfunction "1_1") (pintype "passive"))
      (node (ref "C6") (pin "1") (pinfunction "1_1") (pintype "passive"))
      (node (ref "C8") (pin "1") (pinfunction "1_1") (pintype "passive"))
      (node (ref "J1") (pin "6") (pinfunction "6_6") (pintype "passive"))
      (node (ref "J2") (pin "6") (pinfunction "6_6") (pintype "passive"))
      (node (ref "J3") (pin "6") (pinfunction "6_6") (pintype "passive"))
      (node (ref "J4") (pin "6") (pinfunction "6_6") (pintype "passive"))
      (node (ref "J5") (pin "6") (pinfunction "6_6") (pintype "passive"))
      (node (ref "J6") (pin "1") (pinfunction "1_1") (pintype "passive"))
      (node (ref "PH1") (pin "4") (pinfunction "4_4") (pintype "bidirectional"))
      (node (ref "R1") (pin "2") (pinfunction "2_2") (pintype "passive"))
      (node (ref "R10") (pin "2") (pinfunction "2_2") (pintype "passive"))
      (node (ref "R11") (pin "2") (pinfunction "2_2") (pintype "passive"))
      (node (ref "R12") (pin "2") (pinfunction "2_2") (pintype "passive"))
      (node (ref "R13") (pin "2") (pinfunction "2_2") (pintype "passive"))
      (node (ref "R14") (pin "2") (pinfunction "2_2") (pintype "passive"))
      (node (ref "R15") (pin "2") (pinfunction "2_2") (pintype "passive"))
      (node (ref "R16") (pin "2") (pinfunction "2_2") (pintype "passive"))
      (node (ref "R17") (pin "2") (pinfunction "2_2") (pintype "passive"))
      (node (ref "R18") (pin "2") (pinfunction "2_2") (pintype "passive"))
      (node (ref "R19") (pin "2") (pinfunction "2_2") (pintype "passive"))
      (node (ref "R2") (pin "2") (pinfunction "2_2") (pintype "passive"))
      (node (ref "R20") (pin "2") (pinfunction "2_2") (pintype "passive"))
      (node (ref "R21") (pin "1") (pinfunction "1_1") (pintype "passive"))
      (node (ref "R24") (pin "2") (pinfunction "2_2") (pintype "passive"))
      (node (ref "R26") (pin "2") (pinfunction "2_2") (pintype "passive"))
      (node (ref "R27") (pin "2") (pinfunction "2_2") (pintype "passive"))
      (node (ref "R28") (pin "2") (pinfunction "2_2") (pintype "passive"))
      (node (ref "R29") (pin "2") (pinfunction "2_2") (pintype "passive"))
      (node (ref "R3") (pin "2") (pinfunction "2_2") (pintype "passive"))
      (node (ref "R4") (pin "2") (pinfunction "2_2") (pintype "passive"))
      (node (ref "R5") (pin "2") (pinfunction "2_2") (pintype "passive"))
      (node (ref "R6") (pin "2") (pinfunction "2_2") (pintype "passive"))
      (node (ref "R7") (pin "2") (pinfunction "2_2") (pintype "passive"))
      (node (ref "R8") (pin "2") (pinfunction "2_2") (pintype "passive"))
      (node (ref "R9") (pin "2") (pinfunction "2_2") (pintype "passive"))
      (node (ref "U$12") (pin "5") (pinfunction "VDD_5") (pintype "bidirectional"))
      (node (ref "U$13") (pin "3") (pinfunction "3_3") (pintype "passive"))
      (node (ref "U$13") (pin "4") (pinfunction "4_4") (pintype "passive"))
      (node (ref "U$5") (pin "3") (pinfunction "3_3") (pintype "passive"))
      (node (ref "U$6") (pin "3") (pinfunction "3_3") (pintype "passive"))
      (node (ref "U$9") (pin "1") (pinfunction "VBAT_1") (pintype "bidirectional"))
      (node (ref "U$9") (pin "13") (pinfunction "VDDA_13") (pintype "bidirectional"))
      (node (ref "U$9") (pin "19") (pinfunction "VDD1_19") (pintype "bidirectional"))
      (node (ref "U$9") (pin "32") (pinfunction "VDD2_32") (pintype "bidirectional"))
      (node (ref "U$9") (pin "48") (pinfunction "VDD3_48") (pintype "bidirectional"))
      (node (ref "U$9") (pin "64") (pinfunction "VDD4_64") (pintype "bidirectional"))
      (node (ref "U1") (pin "P$10") (pinfunction "VDD_P$10") (pintype "bidirectional"))
      (node (ref "U1") (pin "P$6") (pinfunction "VDD/NC_P$6") (pintype "bidirectional"))
      (node (ref "U11") (pin "1") (pinfunction "VDD_1") (pintype "power_in"))
      (node (ref "U11") (pin "12") (pinfunction "VDD_12") (pintype "power_in"))
      (node (ref "U2") (pin "P$10") (pinfunction "VDD_P$10") (pintype "bidirectional"))
      (node (ref "U2") (pin "P$6") (pinfunction "VDD/NC_P$6") (pintype "bidirectional"))
      (node (ref "U3") (pin "P$10") (pinfunction "VDD_P$10") (pintype "bidirectional"))
      (node (ref "U3") (pin "P$6") (pinfunction "VDD/NC_P$6") (pintype "bidirectional"))
      (node (ref "U4") (pin "P$10") (pinfunction "VDD_P$10") (pintype "bidirectional"))
      (node (ref "U4") (pin "P$6") (pinfunction "VDD/NC_P$6") (pintype "bidirectional"))
      (node (ref "U5") (pin "P$10") (pinfunction "VDD_P$10") (pintype "bidirectional"))
      (node (ref "U5") (pin "P$6") (pinfunction "VDD/NC_P$6") (pintype "bidirectional"))
      (node (ref "U6") (pin "P$10") (pinfunction "VDD_P$10") (pintype "bidirectional"))
      (node (ref "U6") (pin "P$6") (pinfunction "VDD/NC_P$6") (pintype "bidirectional"))
      (node (ref "U7") (pin "28") (pinfunction "VDDIO_28") (pintype "bidirectional"))
      (node (ref "U7") (pin "3") (pinfunction "VDD_3") (pintype "bidirectional"))
      (node (ref "U8") (pin "24") (pinfunction "VCC_24") (pintype "bidirectional"))
      (node (ref "U9") (pin "24") (pinfunction "VCC_24") (pintype "bidirectional"))
    )
    (net (code "142") (name "unconnected-(U$9-PA0-Pad14)") (class "Default")
      (node (ref "U$9") (pin "14") (pinfunction "PA0_14") (pintype "bidirectional"))
    )
    (net (code "143") (name "unconnected-(U$9-PA1-Pad15)") (class "Default")
      (node (ref "U$9") (pin "15") (pinfunction "PA1_15") (pintype "bidirectional"))
    )
    (net (code "144") (name "unconnected-(U$9-PA8-Pad41)") (class "Default")
      (node (ref "U$9") (pin "41") (pinfunction "PA8_41") (pintype "bidirectional"))
    )
    (net (code "145") (name "unconnected-(U$9-PA11-Pad44)") (class "Default")
      (node (ref "U$9") (pin "44") (pinfunction "PA11_44") (pintype "bidirectional"))
    )
    (net (code "146") (name "unconnected-(U$9-PB5-Pad57)") (class "Default")
      (node (ref "U$9") (pin "57") (pinfunction "PB5_57") (pintype "bidirectional"))
    )
    (net (code "147") (name "unconnected-(U$9-PB8-Pad61)") (class "Default")
      (node (ref "U$9") (pin "61") (pinfunction "PB8_61") (pintype "bidirectional"))
    )
    (net (code "148") (name "unconnected-(U$9-PB9-Pad62)") (class "Default")
      (node (ref "U$9") (pin "62") (pinfunction "PB9_62") (pintype "bidirectional"))
    )
    (net (code "149") (name "unconnected-(U$9-PC0-Pad8)") (class "Default")
      (node (ref "U$9") (pin "8") (pinfunction "PC0_8") (pintype "bidirectional"))
    )
    (net (code "150") (name "unconnected-(U$9-PC1-Pad9)") (class "Default")
      (node (ref "U$9") (pin "9") (pinfunction "PC1_9") (pintype "bidirectional"))
    )
    (net (code "151") (name "unconnected-(U$9-PC2-Pad10)") (class "Default")
      (node (ref "U$9") (pin "10") (pinfunction "PC2_10") (pintype "bidirectional"))
    )
    (net (code "152") (name "unconnected-(U$9-PC3-Pad11)") (class "Default")
      (node (ref "U$9") (pin "11") (pinfunction "PC3_11") (pintype "bidirectional"))
    )
    (net (code "153") (name "unconnected-(U$9-PC6{slash}I2S2_MCK-Pad37)") (class "Default")
      (node (ref "U$9") (pin "37") (pinfunction "PC6/I2S2_MCK_37") (pintype "bidirectional"))
    )
    (net (code "154") (name "unconnected-(U$9-PC7-Pad38)") (class "Default")
      (node (ref "U$9") (pin "38") (pinfunction "PC7_38") (pintype "bidirectional"))
    )
    (net (code "155") (name "unconnected-(U$9-PC8{slash}SDIO_D0-Pad39)") (class "Default")
      (node (ref "U$9") (pin "39") (pinfunction "PC8/SDIO_D0_39") (pintype "bidirectional"))
    )
    (net (code "156") (name "unconnected-(U$9-PC9{slash}SDIO_D1-Pad40)") (class "Default")
      (node (ref "U$9") (pin "40") (pinfunction "PC9/SDIO_D1_40") (pintype "bidirectional"))
    )
    (net (code "157") (name "unconnected-(U$9-PC10{slash}SDIO_D2-Pad51)") (class "Default")
      (node (ref "U$9") (pin "51") (pinfunction "PC10/SDIO_D2_51") (pintype "bidirectional"))
    )
    (net (code "158") (name "unconnected-(U$9-PC11{slash}SDIO_D3-Pad52)") (class "Default")
      (node (ref "U$9") (pin "52") (pinfunction "PC11/SDIO_D3_52") (pintype "bidirectional"))
    )
    (net (code "159") (name "unconnected-(U$9-PC12{slash}SDIO_CLK-Pad53)") (class "Default")
      (node (ref "U$9") (pin "53") (pinfunction "PC12/SDIO_CLK_53") (pintype "bidirectional"))
    )
    (net (code "160") (name "unconnected-(U$9-PC13-Pad2)") (class "Default")
      (node (ref "U$9") (pin "2") (pinfunction "PC13_2") (pintype "bidirectional"))
    )
    (net (code "161") (name "unconnected-(U$9-PD2{slash}SDIO_CMD-Pad54)") (class "Default")
      (node (ref "U$9") (pin "54") (pinfunction "PD2/SDIO_CMD_54") (pintype "bidirectional"))
    )
    (net (code "162") (name "unconnected-(U$12-AHLB-Pad4)") (class "Default")
      (node (ref "U$12") (pin "4") (pinfunction "AHLB_4") (pintype "bidirectional"))
    )
    (net (code "163") (name "unconnected-(U$12-TOGL-Pad6)") (class "Default")
      (node (ref "U$12") (pin "6") (pinfunction "TOGL_6") (pintype "bidirectional"))
    )
    (net (code "164") (name "unconnected-(U11-P0.15-Pad21)") (class "Default")
      (node (ref "U11") (pin "21") (pinfunction "P0.15_21") (pintype "bidirectional"))
    )
    (net (code "165") (name "unconnected-(U11-P0.16-Pad22)") (class "Default")
      (node (ref "U11") (pin "22") (pinfunction "P0.16_22") (pintype "bidirectional"))
    )
    (net (code "166") (name "~{BOOT}") (class "Default")
      (node (ref "R24") (pin "1") (pinfunction "1_1") (pintype "passive"))
      (node (ref "U7") (pin "4") (pinfunction "~{BOOT}_4") (pintype "bidirectional"))
    )
    (net (code "167") (name "~{CS}") (class "Default")
      (node (ref "U7") (pin "18") (pinfunction "~{H_CS}_18") (pintype "bidirectional"))
    )
    (net (code "168") (name "~{INT}") (class "Default")
      (node (ref "U7") (pin "14") (pinfunction "~{H_INT}_14") (pintype "bidirectional"))
    )
    (net (code "169") (name "~{RST}") (class "Default")
      (node (ref "R13") (pin "1") (pinfunction "1_1") (pintype "passive"))
      (node (ref "U7") (pin "11") (pinfunction "~{RST}_11") (pintype "bidirectional"))
    )
  )
)
